# MidiKeys_Right-SCH.net
KiCad netlist of a schematic drawn in EAGLE
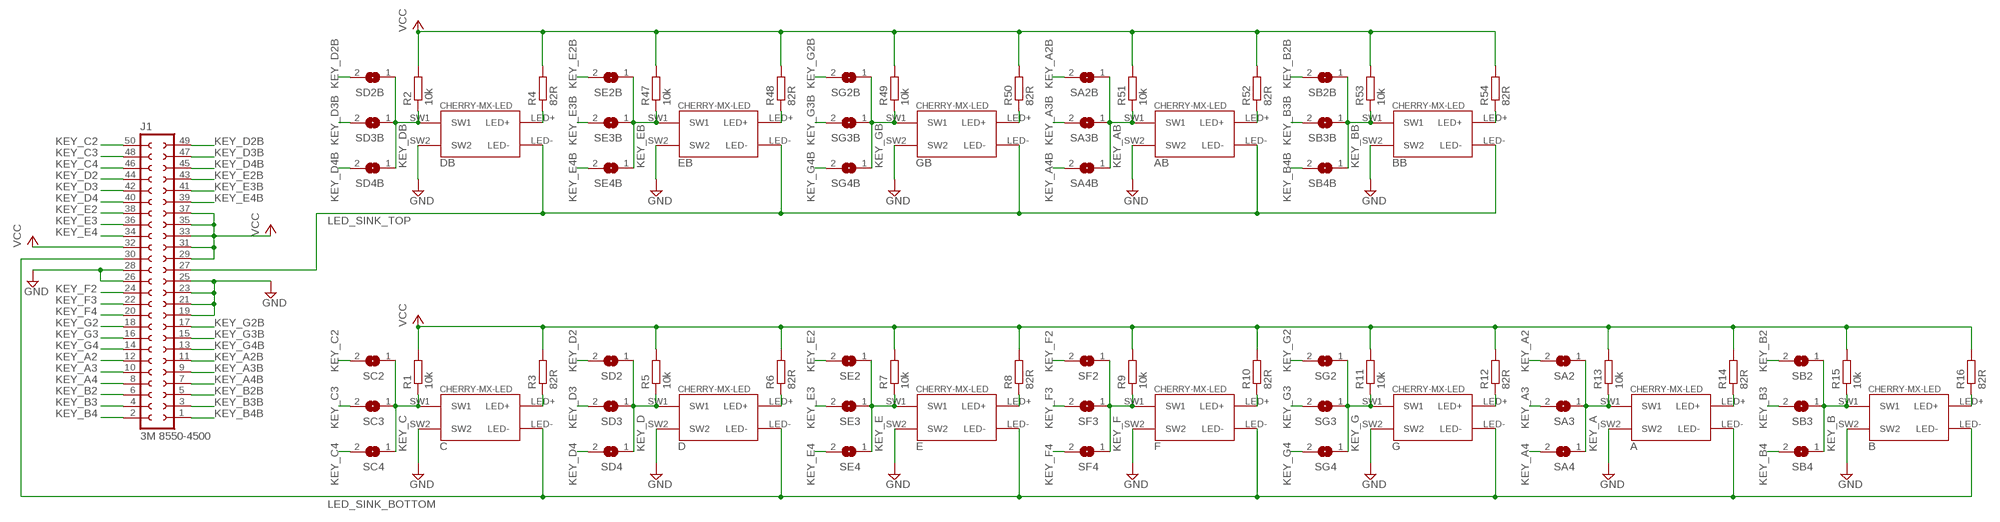
[diagram p0: schematic, sheet 1]

(export (version "E")
  (design (tool "Eeschema 10.0.6"))
  (components
    (comp (ref "A")
      (value "CHERRY-MX-LED")
      (footprint "eagle-import:CHERRY-MX-LED")
      (libsource (lib "eagle-import") (part "CHERRY-MX-LED"))
    )
    (comp (ref "AB")
      (value "CHERRY-MX-LED")
      (footprint "eagle-import:CHERRY-MX-LED")
      (libsource (lib "eagle-import") (part "CHERRY-MX-LED"))
    )
    (comp (ref "B")
      (value "CHERRY-MX-LED")
      (footprint "eagle-import:CHERRY-MX-LED")
      (libsource (lib "eagle-import") (part "CHERRY-MX-LED"))
    )
    (comp (ref "BB")
      (value "CHERRY-MX-LED")
      (footprint "eagle-import:CHERRY-MX-LED")
      (libsource (lib "eagle-import") (part "CHERRY-MX-LED"))
    )
    (comp (ref "C")
      (value "CHERRY-MX-LED")
      (footprint "eagle-import:CHERRY-MX-LED")
      (libsource (lib "eagle-import") (part "CHERRY-MX-LED"))
    )
    (comp (ref "D")
      (value "CHERRY-MX-LED")
      (footprint "eagle-import:CHERRY-MX-LED")
      (libsource (lib "eagle-import") (part "CHERRY-MX-LED"))
    )
    (comp (ref "DB")
      (value "CHERRY-MX-LED")
      (footprint "eagle-import:CHERRY-MX-LED")
      (libsource (lib "eagle-import") (part "CHERRY-MX-LED"))
    )
    (comp (ref "E")
      (value "CHERRY-MX-LED")
      (footprint "eagle-import:CHERRY-MX-LED")
      (libsource (lib "eagle-import") (part "CHERRY-MX-LED"))
    )
    (comp (ref "EB")
      (value "CHERRY-MX-LED")
      (footprint "eagle-import:CHERRY-MX-LED")
      (libsource (lib "eagle-import") (part "CHERRY-MX-LED"))
    )
    (comp (ref "F")
      (value "CHERRY-MX-LED")
      (footprint "eagle-import:CHERRY-MX-LED")
      (libsource (lib "eagle-import") (part "CHERRY-MX-LED"))
    )
    (comp (ref "G")
      (value "CHERRY-MX-LED")
      (footprint "eagle-import:CHERRY-MX-LED")
      (libsource (lib "eagle-import") (part "CHERRY-MX-LED"))
    )
    (comp (ref "GB")
      (value "CHERRY-MX-LED")
      (footprint "eagle-import:CHERRY-MX-LED")
      (libsource (lib "eagle-import") (part "CHERRY-MX-LED"))
    )
    (comp (ref "J1")
      (value "3M 8550-4500")
      (footprint "eagle-import:S50V")
      (libsource (lib "eagle-import") (part "SOCKET-50V"))
    )
    (comp (ref "R1")
      (value "10k")
      (footprint "eagle-import:R0603")
      (libsource (lib "eagle-import") (part "R-EU_R0603"))
    )
    (comp (ref "R2")
      (value "10k")
      (footprint "eagle-import:R0603")
      (libsource (lib "eagle-import") (part "R-EU_R0603"))
    )
    (comp (ref "R3")
      (value "82R")
      (footprint "eagle-import:R0603")
      (libsource (lib "eagle-import") (part "R-EU_R0603"))
    )
    (comp (ref "R4")
      (value "82R")
      (footprint "eagle-import:R0603")
      (libsource (lib "eagle-import") (part "R-EU_R0603"))
    )
    (comp (ref "R5")
      (value "10k")
      (footprint "eagle-import:R0603")
      (libsource (lib "eagle-import") (part "R-EU_R0603"))
    )
    (comp (ref "R6")
      (value "82R")
      (footprint "eagle-import:R0603")
      (libsource (lib "eagle-import") (part "R-EU_R0603"))
    )
    (comp (ref "R7")
      (value "10k")
      (footprint "eagle-import:R0603")
      (libsource (lib "eagle-import") (part "R-EU_R0603"))
    )
    (comp (ref "R8")
      (value "82R")
      (footprint "eagle-import:R0603")
      (libsource (lib "eagle-import") (part "R-EU_R0603"))
    )
    (comp (ref "R9")
      (value "10k")
      (footprint "eagle-import:R0603")
      (libsource (lib "eagle-import") (part "R-EU_R0603"))
    )
    (comp (ref "R10")
      (value "82R")
      (footprint "eagle-import:R0603")
      (libsource (lib "eagle-import") (part "R-EU_R0603"))
    )
    (comp (ref "R11")
      (value "10k")
      (footprint "eagle-import:R0603")
      (libsource (lib "eagle-import") (part "R-EU_R0603"))
    )
    (comp (ref "R12")
      (value "82R")
      (footprint "eagle-import:R0603")
      (libsource (lib "eagle-import") (part "R-EU_R0603"))
    )
    (comp (ref "R13")
      (value "10k")
      (footprint "eagle-import:R0603")
      (libsource (lib "eagle-import") (part "R-EU_R0603"))
    )
    (comp (ref "R14")
      (value "82R")
      (footprint "eagle-import:R0603")
      (libsource (lib "eagle-import") (part "R-EU_R0603"))
    )
    (comp (ref "R15")
      (value "10k")
      (footprint "eagle-import:R0603")
      (libsource (lib "eagle-import") (part "R-EU_R0603"))
    )
    (comp (ref "R16")
      (value "82R")
      (footprint "eagle-import:R0603")
      (libsource (lib "eagle-import") (part "R-EU_R0603"))
    )
    (comp (ref "R47")
      (value "10k")
      (footprint "eagle-import:R0603")
      (libsource (lib "eagle-import") (part "R-EU_R0603"))
    )
    (comp (ref "R48")
      (value "82R")
      (footprint "eagle-import:R0603")
      (libsource (lib "eagle-import") (part "R-EU_R0603"))
    )
    (comp (ref "R49")
      (value "10k")
      (footprint "eagle-import:R0603")
      (libsource (lib "eagle-import") (part "R-EU_R0603"))
    )
    (comp (ref "R50")
      (value "82R")
      (footprint "eagle-import:R0603")
      (libsource (lib "eagle-import") (part "R-EU_R0603"))
    )
    (comp (ref "R51")
      (value "10k")
      (footprint "eagle-import:R0603")
      (libsource (lib "eagle-import") (part "R-EU_R0603"))
    )
    (comp (ref "R52")
      (value "82R")
      (footprint "eagle-import:R0603")
      (libsource (lib "eagle-import") (part "R-EU_R0603"))
    )
    (comp (ref "R53")
      (value "10k")
      (footprint "eagle-import:R0603")
      (libsource (lib "eagle-import") (part "R-EU_R0603"))
    )
    (comp (ref "R54")
      (value "82R")
      (footprint "eagle-import:R0603")
      (libsource (lib "eagle-import") (part "R-EU_R0603"))
    )
    (comp (ref "SA2") (value "SJ") (footprint "eagle-import:SJ") (libsource (lib "eagle-import") (part "SJ")))
    (comp (ref "SA2B")
      (value "SJ")
      (footprint "eagle-import:SJ")
      (libsource (lib "eagle-import") (part "SJ"))
    )
    (comp (ref "SA3") (value "SJ") (footprint "eagle-import:SJ") (libsource (lib "eagle-import") (part "SJ")))
    (comp (ref "SA3B")
      (value "SJ")
      (footprint "eagle-import:SJ")
      (libsource (lib "eagle-import") (part "SJ"))
    )
    (comp (ref "SA4") (value "SJ") (footprint "eagle-import:SJ") (libsource (lib "eagle-import") (part "SJ")))
    (comp (ref "SA4B")
      (value "SJ")
      (footprint "eagle-import:SJ")
      (libsource (lib "eagle-import") (part "SJ"))
    )
    (comp (ref "SB2") (value "SJ") (footprint "eagle-import:SJ") (libsource (lib "eagle-import") (part "SJ")))
    (comp (ref "SB2B")
      (value "SJ")
      (footprint "eagle-import:SJ")
      (libsource (lib "eagle-import") (part "SJ"))
    )
    (comp (ref "SB3") (value "SJ") (footprint "eagle-import:SJ") (libsource (lib "eagle-import") (part "SJ")))
    (comp (ref "SB3B")
      (value "SJ")
      (footprint "eagle-import:SJ")
      (libsource (lib "eagle-import") (part "SJ"))
    )
    (comp (ref "SB4") (value "SJ") (footprint "eagle-import:SJ") (libsource (lib "eagle-import") (part "SJ")))
    (comp (ref "SB4B")
      (value "SJ")
      (footprint "eagle-import:SJ")
      (libsource (lib "eagle-import") (part "SJ"))
    )
    (comp (ref "SC2") (value "SJ") (footprint "eagle-import:SJ") (libsource (lib "eagle-import") (part "SJ")))
    (comp (ref "SC3") (value "SJ") (footprint "eagle-import:SJ") (libsource (lib "eagle-import") (part "SJ")))
    (comp (ref "SC4") (value "SJ") (footprint "eagle-import:SJ") (libsource (lib "eagle-import") (part "SJ")))
    (comp (ref "SD2") (value "SJ") (footprint "eagle-import:SJ") (libsource (lib "eagle-import") (part "SJ")))
    (comp (ref "SD2B")
      (value "SJ")
      (footprint "eagle-import:SJ")
      (libsource (lib "eagle-import") (part "SJ"))
    )
    (comp (ref "SD3") (value "SJ") (footprint "eagle-import:SJ") (libsource (lib "eagle-import") (part "SJ")))
    (comp (ref "SD3B")
      (value "SJ")
      (footprint "eagle-import:SJ")
      (libsource (lib "eagle-import") (part "SJ"))
    )
    (comp (ref "SD4") (value "SJ") (footprint "eagle-import:SJ") (libsource (lib "eagle-import") (part "SJ")))
    (comp (ref "SD4B")
      (value "SJ")
      (footprint "eagle-import:SJ")
      (libsource (lib "eagle-import") (part "SJ"))
    )
    (comp (ref "SE2") (value "SJ") (footprint "eagle-import:SJ") (libsource (lib "eagle-import") (part "SJ")))
    (comp (ref "SE2B")
      (value "SJ")
      (footprint "eagle-import:SJ")
      (libsource (lib "eagle-import") (part "SJ"))
    )
    (comp (ref "SE3") (value "SJ") (footprint "eagle-import:SJ") (libsource (lib "eagle-import") (part "SJ")))
    (comp (ref "SE3B")
      (value "SJ")
      (footprint "eagle-import:SJ")
      (libsource (lib "eagle-import") (part "SJ"))
    )
    (comp (ref "SE4") (value "SJ") (footprint "eagle-import:SJ") (libsource (lib "eagle-import") (part "SJ")))
    (comp (ref "SE4B")
      (value "SJ")
      (footprint "eagle-import:SJ")
      (libsource (lib "eagle-import") (part "SJ"))
    )
    (comp (ref "SF2") (value "SJ") (footprint "eagle-import:SJ") (libsource (lib "eagle-import") (part "SJ")))
    (comp (ref "SF3") (value "SJ") (footprint "eagle-import:SJ") (libsource (lib "eagle-import") (part "SJ")))
    (comp (ref "SF4") (value "SJ") (footprint "eagle-import:SJ") (libsource (lib "eagle-import") (part "SJ")))
    (comp (ref "SG2") (value "SJ") (footprint "eagle-import:SJ") (libsource (lib "eagle-import") (part "SJ")))
    (comp (ref "SG2B")
      (value "SJ")
      (footprint "eagle-import:SJ")
      (libsource (lib "eagle-import") (part "SJ"))
    )
    (comp (ref "SG3") (value "SJ") (footprint "eagle-import:SJ") (libsource (lib "eagle-import") (part "SJ")))
    (comp (ref "SG3B")
      (value "SJ")
      (footprint "eagle-import:SJ")
      (libsource (lib "eagle-import") (part "SJ"))
    )
    (comp (ref "SG4") (value "SJ") (footprint "eagle-import:SJ") (libsource (lib "eagle-import") (part "SJ")))
    (comp (ref "SG4B")
      (value "SJ")
      (footprint "eagle-import:SJ")
      (libsource (lib "eagle-import") (part "SJ"))
    )
  )
  (nets
    (net (code "1") (name "/KEY_A") (class "Default")
      (node (ref "A") (pin "SW1") (pinfunction "SW1_SW1") (pintype "bidirectional"))
      (node (ref "R13") (pin "1") (pinfunction "1_1") (pintype "passive"))
      (node (ref "SA2") (pin "1") (pinfunction "1_1") (pintype "passive"))
      (node (ref "SA3") (pin "1") (pinfunction "1_1") (pintype "passive"))
      (node (ref "SA4") (pin "1") (pinfunction "1_1") (pintype "passive"))
    )
    (net (code "2") (name "/KEY_A2") (class "Default")
      (node (ref "J1") (pin "12") (pinfunction "12_12") (pintype "passive"))
      (node (ref "SA2") (pin "2") (pinfunction "2_2") (pintype "passive"))
    )
    (net (code "3") (name "/KEY_A2B") (class "Default")
      (node (ref "J1") (pin "11") (pinfunction "11_11") (pintype "passive"))
      (node (ref "SA2B") (pin "2") (pinfunction "2_2") (pintype "passive"))
    )
    (net (code "4") (name "/KEY_A3") (class "Default")
      (node (ref "J1") (pin "10") (pinfunction "10_10") (pintype "passive"))
      (node (ref "SA3") (pin "2") (pinfunction "2_2") (pintype "passive"))
    )
    (net (code "5") (name "/KEY_A3B") (class "Default")
      (node (ref "J1") (pin "9") (pinfunction "9_9") (pintype "passive"))
      (node (ref "SA3B") (pin "2") (pinfunction "2_2") (pintype "passive"))
    )
    (net (code "6") (name "/KEY_A4") (class "Default")
      (node (ref "J1") (pin "8") (pinfunction "8_8") (pintype "passive"))
      (node (ref "SA4") (pin "2") (pinfunction "2_2") (pintype "passive"))
    )
    (net (code "7") (name "/KEY_A4B") (class "Default")
      (node (ref "J1") (pin "7") (pinfunction "7_7") (pintype "passive"))
      (node (ref "SA4B") (pin "2") (pinfunction "2_2") (pintype "passive"))
    )
    (net (code "8") (name "/KEY_AB") (class "Default")
      (node (ref "AB") (pin "SW1") (pinfunction "SW1_SW1") (pintype "bidirectional"))
      (node (ref "R51") (pin "1") (pinfunction "1_1") (pintype "passive"))
      (node (ref "SA2B") (pin "1") (pinfunction "1_1") (pintype "passive"))
      (node (ref "SA3B") (pin "1") (pinfunction "1_1") (pintype "passive"))
      (node (ref "SA4B") (pin "1") (pinfunction "1_1") (pintype "passive"))
    )
    (net (code "9") (name "/KEY_B") (class "Default")
      (node (ref "B") (pin "SW1") (pinfunction "SW1_SW1") (pintype "bidirectional"))
      (node (ref "R15") (pin "1") (pinfunction "1_1") (pintype "passive"))
      (node (ref "SB2") (pin "1") (pinfunction "1_1") (pintype "passive"))
      (node (ref "SB3") (pin "1") (pinfunction "1_1") (pintype "passive"))
      (node (ref "SB4") (pin "1") (pinfunction "1_1") (pintype "passive"))
    )
    (net (code "10") (name "/KEY_B2") (class "Default")
      (node (ref "J1") (pin "6") (pinfunction "6_6") (pintype "passive"))
      (node (ref "SB2") (pin "2") (pinfunction "2_2") (pintype "passive"))
    )
    (net (code "11") (name "/KEY_B2B") (class "Default")
      (node (ref "J1") (pin "5") (pinfunction "5_5") (pintype "passive"))
      (node (ref "SB2B") (pin "2") (pinfunction "2_2") (pintype "passive"))
    )
    (net (code "12") (name "/KEY_B3") (class "Default")
      (node (ref "J1") (pin "4") (pinfunction "4_4") (pintype "passive"))
      (node (ref "SB3") (pin "2") (pinfunction "2_2") (pintype "passive"))
    )
    (net (code "13") (name "/KEY_B3B") (class "Default")
      (node (ref "J1") (pin "3") (pinfunction "3_3") (pintype "passive"))
      (node (ref "SB3B") (pin "2") (pinfunction "2_2") (pintype "passive"))
    )
    (net (code "14") (name "/KEY_B4") (class "Default")
      (node (ref "J1") (pin "2") (pinfunction "2_2") (pintype "passive"))
      (node (ref "SB4") (pin "2") (pinfunction "2_2") (pintype "passive"))
    )
    (net (code "15") (name "/KEY_B4B") (class "Default")
      (node (ref "J1") (pin "1") (pinfunction "1_1") (pintype "passive"))
      (node (ref "SB4B") (pin "2") (pinfunction "2_2") (pintype "passive"))
    )
    (net (code "16") (name "/KEY_BB") (class "Default")
      (node (ref "BB") (pin "SW1") (pinfunction "SW1_SW1") (pintype "bidirectional"))
      (node (ref "R53") (pin "1") (pinfunction "1_1") (pintype "passive"))
      (node (ref "SB2B") (pin "1") (pinfunction "1_1") (pintype "passive"))
      (node (ref "SB3B") (pin "1") (pinfunction "1_1") (pintype "passive"))
      (node (ref "SB4B") (pin "1") (pinfunction "1_1") (pintype "passive"))
    )
    (net (code "17") (name "/KEY_C") (class "Default")
      (node (ref "C") (pin "SW1") (pinfunction "SW1_SW1") (pintype "bidirectional"))
      (node (ref "R1") (pin "1") (pinfunction "1_1") (pintype "passive"))
      (node (ref "SC2") (pin "1") (pinfunction "1_1") (pintype "passive"))
      (node (ref "SC3") (pin "1") (pinfunction "1_1") (pintype "passive"))
      (node (ref "SC4") (pin "1") (pinfunction "1_1") (pintype "passive"))
    )
    (net (code "18") (name "/KEY_C2") (class "Default")
      (node (ref "J1") (pin "50") (pinfunction "50_50") (pintype "passive"))
      (node (ref "SC2") (pin "2") (pinfunction "2_2") (pintype "passive"))
    )
    (net (code "19") (name "/KEY_C3") (class "Default")
      (node (ref "J1") (pin "48") (pinfunction "48_48") (pintype "passive"))
      (node (ref "SC3") (pin "2") (pinfunction "2_2") (pintype "passive"))
    )
    (net (code "20") (name "/KEY_C4") (class "Default")
      (node (ref "J1") (pin "46") (pinfunction "46_46") (pintype "passive"))
      (node (ref "SC4") (pin "2") (pinfunction "2_2") (pintype "passive"))
    )
    (net (code "21") (name "/KEY_D") (class "Default")
      (node (ref "D") (pin "SW1") (pinfunction "SW1_SW1") (pintype "bidirectional"))
      (node (ref "R5") (pin "1") (pinfunction "1_1") (pintype "passive"))
      (node (ref "SD2") (pin "1") (pinfunction "1_1") (pintype "passive"))
      (node (ref "SD3") (pin "1") (pinfunction "1_1") (pintype "passive"))
      (node (ref "SD4") (pin "1") (pinfunction "1_1") (pintype "passive"))
    )
    (net (code "22") (name "/KEY_D2") (class "Default")
      (node (ref "J1") (pin "44") (pinfunction "44_44") (pintype "passive"))
      (node (ref "SD2") (pin "2") (pinfunction "2_2") (pintype "passive"))
    )
    (net (code "23") (name "/KEY_D2B") (class "Default")
      (node (ref "J1") (pin "49") (pinfunction "49_49") (pintype "passive"))
      (node (ref "SD2B") (pin "2") (pinfunction "2_2") (pintype "passive"))
    )
    (net (code "24") (name "/KEY_D3") (class "Default")
      (node (ref "J1") (pin "42") (pinfunction "42_42") (pintype "passive"))
      (node (ref "SD3") (pin "2") (pinfunction "2_2") (pintype "passive"))
    )
    (net (code "25") (name "/KEY_D3B") (class "Default")
      (node (ref "J1") (pin "47") (pinfunction "47_47") (pintype "passive"))
      (node (ref "SD3B") (pin "2") (pinfunction "2_2") (pintype "passive"))
    )
    (net (code "26") (name "/KEY_D4") (class "Default")
      (node (ref "J1") (pin "40") (pinfunction "40_40") (pintype "passive"))
      (node (ref "SD4") (pin "2") (pinfunction "2_2") (pintype "passive"))
    )
    (net (code "27") (name "/KEY_D4B") (class "Default")
      (node (ref "J1") (pin "45") (pinfunction "45_45") (pintype "passive"))
      (node (ref "SD4B") (pin "2") (pinfunction "2_2") (pintype "passive"))
    )
    (net (code "28") (name "/KEY_DB") (class "Default")
      (node (ref "DB") (pin "SW1") (pinfunction "SW1_SW1") (pintype "bidirectional"))
      (node (ref "R2") (pin "1") (pinfunction "1_1") (pintype "passive"))
      (node (ref "SD2B") (pin "1") (pinfunction "1_1") (pintype "passive"))
      (node (ref "SD3B") (pin "1") (pinfunction "1_1") (pintype "passive"))
      (node (ref "SD4B") (pin "1") (pinfunction "1_1") (pintype "passive"))
    )
    (net (code "29") (name "/KEY_E") (class "Default")
      (node (ref "E") (pin "SW1") (pinfunction "SW1_SW1") (pintype "bidirectional"))
      (node (ref "R7") (pin "1") (pinfunction "1_1") (pintype "passive"))
      (node (ref "SE2") (pin "1") (pinfunction "1_1") (pintype "passive"))
      (node (ref "SE3") (pin "1") (pinfunction "1_1") (pintype "passive"))
      (node (ref "SE4") (pin "1") (pinfunction "1_1") (pintype "passive"))
    )
    (net (code "30") (name "/KEY_E2") (class "Default")
      (node (ref "J1") (pin "38") (pinfunction "38_38") (pintype "passive"))
      (node (ref "SE2") (pin "2") (pinfunction "2_2") (pintype "passive"))
    )
    (net (code "31") (name "/KEY_E2B") (class "Default")
      (node (ref "J1") (pin "43") (pinfunction "43_43") (pintype "passive"))
      (node (ref "SE2B") (pin "2") (pinfunction "2_2") (pintype "passive"))
    )
    (net (code "32") (name "/KEY_E3") (class "Default")
      (node (ref "J1") (pin "36") (pinfunction "36_36") (pintype "passive"))
      (node (ref "SE3") (pin "2") (pinfunction "2_2") (pintype "passive"))
    )
    (net (code "33") (name "/KEY_E3B") (class "Default")
      (node (ref "J1") (pin "41") (pinfunction "41_41") (pintype "passive"))
      (node (ref "SE3B") (pin "2") (pinfunction "2_2") (pintype "passive"))
    )
    (net (code "34") (name "/KEY_E4") (class "Default")
      (node (ref "J1") (pin "34") (pinfunction "34_34") (pintype "passive"))
      (node (ref "SE4") (pin "2") (pinfunction "2_2") (pintype "passive"))
    )
    (net (code "35") (name "/KEY_E4B") (class "Default")
      (node (ref "J1") (pin "39") (pinfunction "39_39") (pintype "passive"))
      (node (ref "SE4B") (pin "2") (pinfunction "2_2") (pintype "passive"))
    )
    (net (code "36") (name "/KEY_EB") (class "Default")
      (node (ref "EB") (pin "SW1") (pinfunction "SW1_SW1") (pintype "bidirectional"))
      (node (ref "R47") (pin "1") (pinfunction "1_1") (pintype "passive"))
      (node (ref "SE2B") (pin "1") (pinfunction "1_1") (pintype "passive"))
      (node (ref "SE3B") (pin "1") (pinfunction "1_1") (pintype "passive"))
      (node (ref "SE4B") (pin "1") (pinfunction "1_1") (pintype "passive"))
    )
    (net (code "37") (name "/KEY_F") (class "Default")
      (node (ref "F") (pin "SW1") (pinfunction "SW1_SW1") (pintype "bidirectional"))
      (node (ref "R9") (pin "1") (pinfunction "1_1") (pintype "passive"))
      (node (ref "SF2") (pin "1") (pinfunction "1_1") (pintype "passive"))
      (node (ref "SF3") (pin "1") (pinfunction "1_1") (pintype "passive"))
      (node (ref "SF4") (pin "1") (pinfunction "1_1") (pintype "passive"))
    )
    (net (code "38") (name "/KEY_F2") (class "Default")
      (node (ref "J1") (pin "24") (pinfunction "24_24") (pintype "passive"))
      (node (ref "SF2") (pin "2") (pinfunction "2_2") (pintype "passive"))
    )
    (net (code "39") (name "/KEY_F3") (class "Default")
      (node (ref "J1") (pin "22") (pinfunction "22_22") (pintype "passive"))
      (node (ref "SF3") (pin "2") (pinfunction "2_2") (pintype "passive"))
    )
    (net (code "40") (name "/KEY_F4") (class "Default")
      (node (ref "J1") (pin "20") (pinfunction "20_20") (pintype "passive"))
      (node (ref "SF4") (pin "2") (pinfunction "2_2") (pintype "passive"))
    )
    (net (code "41") (name "/KEY_G") (class "Default")
      (node (ref "G") (pin "SW1") (pinfunction "SW1_SW1") (pintype "bidirectional"))
      (node (ref "R11") (pin "1") (pinfunction "1_1") (pintype "passive"))
      (node (ref "SG2") (pin "1") (pinfunction "1_1") (pintype "passive"))
      (node (ref "SG3") (pin "1") (pinfunction "1_1") (pintype "passive"))
      (node (ref "SG4") (pin "1") (pinfunction "1_1") (pintype "passive"))
    )
    (net (code "42") (name "/KEY_G2") (class "Default")
      (node (ref "J1") (pin "18") (pinfunction "18_18") (pintype "passive"))
      (node (ref "SG2") (pin "2") (pinfunction "2_2") (pintype "passive"))
    )
    (net (code "43") (name "/KEY_G2B") (class "Default")
      (node (ref "J1") (pin "17") (pinfunction "17_17") (pintype "passive"))
      (node (ref "SG2B") (pin "2") (pinfunction "2_2") (pintype "passive"))
    )
    (net (code "44") (name "/KEY_G3") (class "Default")
      (node (ref "J1") (pin "16") (pinfunction "16_16") (pintype "passive"))
      (node (ref "SG3") (pin "2") (pinfunction "2_2") (pintype "passive"))
    )
    (net (code "45") (name "/KEY_G3B") (class "Default")
      (node (ref "J1") (pin "15") (pinfunction "15_15") (pintype "passive"))
      (node (ref "SG3B") (pin "2") (pinfunction "2_2") (pintype "passive"))
    )
    (net (code "46") (name "/KEY_G4") (class "Default")
      (node (ref "J1") (pin "14") (pinfunction "14_14") (pintype "passive"))
      (node (ref "SG4") (pin "2") (pinfunction "2_2") (pintype "passive"))
    )
    (net (code "47") (name "/KEY_G4B") (class "Default")
      (node (ref "J1") (pin "13") (pinfunction "13_13") (pintype "passive"))
      (node (ref "SG4B") (pin "2") (pinfunction "2_2") (pintype "passive"))
    )
    (net (code "48") (name "/KEY_GB") (class "Default")
      (node (ref "GB") (pin "SW1") (pinfunction "SW1_SW1") (pintype "bidirectional"))
      (node (ref "R49") (pin "1") (pinfunction "1_1") (pintype "passive"))
      (node (ref "SG2B") (pin "1") (pinfunction "1_1") (pintype "passive"))
      (node (ref "SG3B") (pin "1") (pinfunction "1_1") (pintype "passive"))
      (node (ref "SG4B") (pin "1") (pinfunction "1_1") (pintype "passive"))
    )
    (net (code "49") (name "/LED_SINK_BOTTOM") (class "Default")
      (node (ref "A") (pin "LED-") (pinfunction "LED-_LED-") (pintype "bidirectional"))
      (node (ref "B") (pin "LED-") (pinfunction "LED-_LED-") (pintype "bidirectional"))
      (node (ref "C") (pin "LED-") (pinfunction "LED-_LED-") (pintype "bidirectional"))
      (node (ref "D") (pin "LED-") (pinfunction "LED-_LED-") (pintype "bidirectional"))
      (node (ref "E") (pin "LED-") (pinfunction "LED-_LED-") (pintype "bidirectional"))
      (node (ref "F") (pin "LED-") (pinfunction "LED-_LED-") (pintype "bidirectional"))
      (node (ref "G") (pin "LED-") (pinfunction "LED-_LED-") (pintype "bidirectional"))
      (node (ref "J1") (pin "30") (pinfunction "30_30") (pintype "passive"))
    )
    (net (code "50") (name "/LED_SINK_TOP") (class "Default")
      (node (ref "AB") (pin "LED-") (pinfunction "LED-_LED-") (pintype "bidirectional"))
      (node (ref "BB") (pin "LED-") (pinfunction "LED-_LED-") (pintype "bidirectional"))
      (node (ref "DB") (pin "LED-") (pinfunction "LED-_LED-") (pintype "bidirectional"))
      (node (ref "EB") (pin "LED-") (pinfunction "LED-_LED-") (pintype "bidirectional"))
      (node (ref "GB") (pin "LED-") (pinfunction "LED-_LED-") (pintype "bidirectional"))
      (node (ref "J1") (pin "27") (pinfunction "27_27") (pintype "passive"))
    )
    (net (code "51") (name "GND") (class "Default")
      (node (ref "A") (pin "SW2") (pinfunction "SW2_SW2") (pintype "bidirectional"))
      (node (ref "AB") (pin "SW2") (pinfunction "SW2_SW2") (pintype "bidirectional"))
      (node (ref "B") (pin "SW2") (pinfunction "SW2_SW2") (pintype "bidirectional"))
      (node (ref "BB") (pin "SW2") (pinfunction "SW2_SW2") (pintype "bidirectional"))
      (node (ref "C") (pin "SW2") (pinfunction "SW2_SW2") (pintype "bidirectional"))
      (node (ref "D") (pin "SW2") (pinfunction "SW2_SW2") (pintype "bidirectional"))
      (node (ref "DB") (pin "SW2") (pinfunction "SW2_SW2") (pintype "bidirectional"))
      (node (ref "E") (pin "SW2") (pinfunction "SW2_SW2") (pintype "bidirectional"))
      (node (ref "EB") (pin "SW2") (pinfunction "SW2_SW2") (pintype "bidirectional"))
      (node (ref "F") (pin "SW2") (pinfunction "SW2_SW2") (pintype "bidirectional"))
      (node (ref "G") (pin "SW2") (pinfunction "SW2_SW2") (pintype "bidirectional"))
      (node (ref "GB") (pin "SW2") (pinfunction "SW2_SW2") (pintype "bidirectional"))
      (node (ref "J1") (pin "19") (pinfunction "19_19") (pintype "passive"))
      (node (ref "J1") (pin "21") (pinfunction "21_21") (pintype "passive"))
      (node (ref "J1") (pin "23") (pinfunction "23_23") (pintype "passive"))
      (node (ref "J1") (pin "25") (pinfunction "25_25") (pintype "passive"))
      (node (ref "J1") (pin "26") (pinfunction "26_26") (pintype "passive"))
      (node (ref "J1") (pin "28") (pinfunction "28_28") (pintype "passive"))
    )
    (net (code "52") (name "Net-(A-PadLED+)") (class "Default")
      (node (ref "A") (pin "LED+") (pinfunction "LED+_LED+") (pintype "bidirectional"))
      (node (ref "R14") (pin "1") (pinfunction "1_1") (pintype "passive"))
    )
    (net (code "53") (name "Net-(AB-PadLED+)") (class "Default")
      (node (ref "AB") (pin "LED+") (pinfunction "LED+_LED+") (pintype "bidirectional"))
      (node (ref "R52") (pin "1") (pinfunction "1_1") (pintype "passive"))
    )
    (net (code "54") (name "Net-(B-PadLED+)") (class "Default")
      (node (ref "B") (pin "LED+") (pinfunction "LED+_LED+") (pintype "bidirectional"))
      (node (ref "R16") (pin "1") (pinfunction "1_1") (pintype "passive"))
    )
    (net (code "55") (name "Net-(BB-PadLED+)") (class "Default")
      (node (ref "BB") (pin "LED+") (pinfunction "LED+_LED+") (pintype "bidirectional"))
      (node (ref "R54") (pin "1") (pinfunction "1_1") (pintype "passive"))
    )
    (net (code "56") (name "Net-(C-PadLED+)") (class "Default")
      (node (ref "C") (pin "LED+") (pinfunction "LED+_LED+") (pintype "bidirectional"))
      (node (ref "R3") (pin "1") (pinfunction "1_1") (pintype "passive"))
    )
    (net (code "57") (name "Net-(D-PadLED+)") (class "Default")
      (node (ref "D") (pin "LED+") (pinfunction "LED+_LED+") (pintype "bidirectional"))
      (node (ref "R6") (pin "1") (pinfunction "1_1") (pintype "passive"))
    )
    (net (code "58") (name "Net-(DB-PadLED+)") (class "Default")
      (node (ref "DB") (pin "LED+") (pinfunction "LED+_LED+") (pintype "bidirectional"))
      (node (ref "R4") (pin "1") (pinfunction "1_1") (pintype "passive"))
    )
    (net (code "59") (name "Net-(E-PadLED+)") (class "Default")
      (node (ref "E") (pin "LED+") (pinfunction "LED+_LED+") (pintype "bidirectional"))
      (node (ref "R8") (pin "1") (pinfunction "1_1") (pintype "passive"))
    )
    (net (code "60") (name "Net-(EB-PadLED+)") (class "Default")
      (node (ref "EB") (pin "LED+") (pinfunction "LED+_LED+") (pintype "bidirectional"))
      (node (ref "R48") (pin "1") (pinfunction "1_1") (pintype "passive"))
    )
    (net (code "61") (name "Net-(F-PadLED+)") (class "Default")
      (node (ref "F") (pin "LED+") (pinfunction "LED+_LED+") (pintype "bidirectional"))
      (node (ref "R10") (pin "1") (pinfunction "1_1") (pintype "passive"))
    )
    (net (code "62") (name "Net-(G-PadLED+)") (class "Default")
      (node (ref "G") (pin "LED+") (pinfunction "LED+_LED+") (pintype "bidirectional"))
      (node (ref "R12") (pin "1") (pinfunction "1_1") (pintype "passive"))
    )
    (net (code "63") (name "Net-(GB-PadLED+)") (class "Default")
      (node (ref "GB") (pin "LED+") (pinfunction "LED+_LED+") (pintype "bidirectional"))
      (node (ref "R50") (pin "1") (pinfunction "1_1") (pintype "passive"))
    )
    (net (code "64") (name "VCC") (class "Default")
      (node (ref "J1") (pin "29") (pinfunction "29_29") (pintype "passive"))
      (node (ref "J1") (pin "31") (pinfunction "31_31") (pintype "passive"))
      (node (ref "J1") (pin "32") (pinfunction "32_32") (pintype "passive"))
      (node (ref "J1") (pin "33") (pinfunction "33_33") (pintype "passive"))
      (node (ref "J1") (pin "35") (pinfunction "35_35") (pintype "passive"))
      (node (ref "J1") (pin "37") (pinfunction "37_37") (pintype "passive"))
      (node (ref "R1") (pin "2") (pinfunction "2_2") (pintype "passive"))
      (node (ref "R10") (pin "2") (pinfunction "2_2") (pintype "passive"))
      (node (ref "R11") (pin "2") (pinfunction "2_2") (pintype "passive"))
      (node (ref "R12") (pin "2") (pinfunction "2_2") (pintype "passive"))
      (node (ref "R13") (pin "2") (pinfunction "2_2") (pintype "passive"))
      (node (ref "R14") (pin "2") (pinfunction "2_2") (pintype "passive"))
      (node (ref "R15") (pin "2") (pinfunction "2_2") (pintype "passive"))
      (node (ref "R16") (pin "2") (pinfunction "2_2") (pintype "passive"))
      (node (ref "R2") (pin "2") (pinfunction "2_2") (pintype "passive"))
      (node (ref "R3") (pin "2") (pinfunction "2_2") (pintype "passive"))
      (node (ref "R4") (pin "2") (pinfunction "2_2") (pintype "passive"))
      (node (ref "R47") (pin "2") (pinfunction "2_2") (pintype "passive"))
      (node (ref "R48") (pin "2") (pinfunction "2_2") (pintype "passive"))
      (node (ref "R49") (pin "2") (pinfunction "2_2") (pintype "passive"))
      (node (ref "R5") (pin "2") (pinfunction "2_2") (pintype "passive"))
      (node (ref "R50") (pin "2") (pinfunction "2_2") (pintype "passive"))
      (node (ref "R51") (pin "2") (pinfunction "2_2") (pintype "passive"))
      (node (ref "R52") (pin "2") (pinfunction "2_2") (pintype "passive"))
      (node (ref "R53") (pin "2") (pinfunction "2_2") (pintype "passive"))
      (node (ref "R54") (pin "2") (pinfunction "2_2") (pintype "passive"))
      (node (ref "R6") (pin "2") (pinfunction "2_2") (pintype "passive"))
      (node (ref "R7") (pin "2") (pinfunction "2_2") (pintype "passive"))
      (node (ref "R8") (pin "2") (pinfunction "2_2") (pintype "passive"))
      (node (ref "R9") (pin "2") (pinfunction "2_2") (pintype "passive"))
    )
  )
)
